# IO.net
KiCad netlist of a schematic drawn in Altium Designer
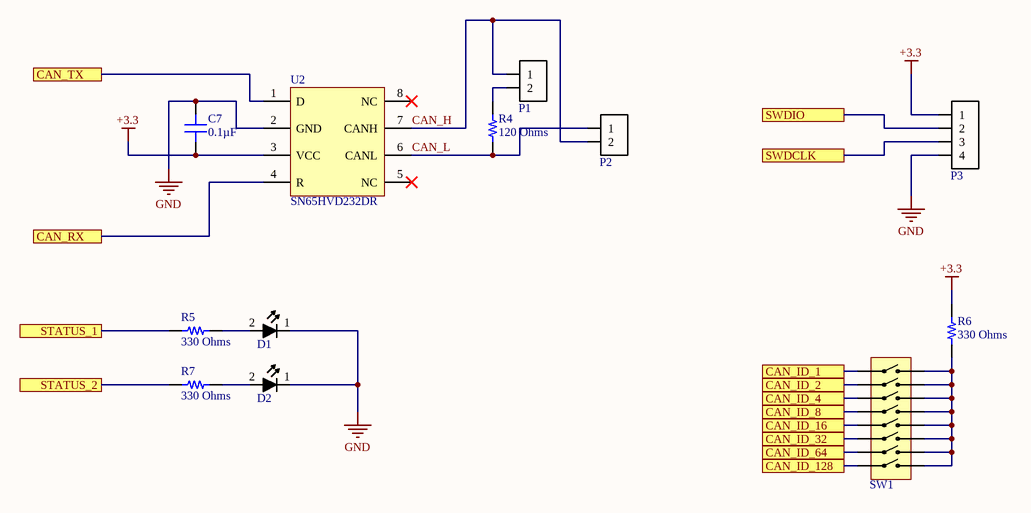
[diagram p0: IO.SchDoc]

(export (version "E")
  (design (tool "Eeschema 10.0.6"))
  (components
    (comp (ref "C7")
      (value "0.1µF")
      (footprint "CAP 0805_2012")
      (description "CAP CER 0805 0.1UF 50V X7R")
      (fields (field (name "PART NUMBER") "C0805X104K5RAC3316") (field (name "MANUFACTURER") "KEMET"))
      (libsource (lib "Celestial Altium Library - altium_library") (part "Capacitor"))
    )
    (comp (ref "D1")
      (value "diode_4")
      (footprint "chip_0603_LED")
      (description "LED, Blue, 0603, Low current, HELI2 Series")
      (fields (field (name "PART NUMBER") "DIO-00049") (field (name "MANUFACTURER") "Kingbright"))
      (libsource (lib "cwrubotix_library") (part "diode_4"))
    )
    (comp (ref "D2")
      (value "diode_4")
      (footprint "chip_0603_LED")
      (description "LED, Blue, 0603, Low current, HELI2 Series")
      (fields (field (name "PART NUMBER") "DIO-00049") (field (name "MANUFACTURER") "Kingbright"))
      (libsource (lib "cwrubotix_library") (part "diode_4"))
    )
    (comp (ref "P1")
      (value "conn-2x1_0")
      (footprint "hddr_2x1_0")
      (description "Header, 2x1, 0.1\"")
      (fields (field (name "PART NUMBER") "CONN-00055") (field (name "MANUFACTURER") "Samtec"))
      (libsource (lib "Connectors") (part "conn-2x1_0"))
    )
    (comp (ref "P2")
      (value "conn-2x1_0")
      (footprint "TERM_3.50MM_2x1_0")
      (description "Term Blk, 2 Pos, 8A, 3.5mm Pitch, Screwless")
      (fields (field (name "PART NUMBER") "CONN-00023") (field (name "MANUFACTURER") "Phoenix Contact"))
      (libsource (lib "Connectors") (part "conn-2x1_0"))
    )
    (comp (ref "P3")
      (value "conn-4x1_0")
      (footprint "HDDR_4x1_0")
      (description "Header 4x1, 0.1\"")
      (fields (field (name "PART NUMBER") "CONN-00029"))
      (libsource (lib "Connectors") (part "conn-4x1_0"))
    )
    (comp (ref "R4")
      (value "120 Ohms")
      (footprint "RES 0805_2012")
      (description "CRGCQ 0805 120R 1%")
      (fields
        (field (name "PART NUMBER") "CRGCQ0805F120R")
        (field (name "MANUFACTURER") "TE Connectivity Passive Product")
      )
      (libsource (lib "Celestial Altium Library - altium_library") (part "Resistor"))
    )
    (comp (ref "R5")
      (value "330 Ohms")
      (footprint "RES 0603_1608")
      (description "RES 330 OHM 5% 1/8W 0603")
      (fields
        (field (name "PART NUMBER") "RK73B1JTTD331J")
        (field (name "MANUFACTURER") "KOA Speer Electronics, Inc.")
      )
      (libsource (lib "Celestial Altium Library - altium_library") (part "Resistor"))
    )
    (comp (ref "R6")
      (value "330 Ohms")
      (footprint "RES 0603_1608")
      (description "RES 330 OHM 5% 1/8W 0603")
      (fields
        (field (name "PART NUMBER") "RK73B1JTTD331J")
        (field (name "MANUFACTURER") "KOA Speer Electronics, Inc.")
      )
      (libsource (lib "Celestial Altium Library - altium_library") (part "Resistor"))
    )
    (comp (ref "R7")
      (value "330 Ohms")
      (footprint "RES 0603_1608")
      (description "RES 330 OHM 5% 1/8W 0603")
      (fields
        (field (name "PART NUMBER") "RK73B1JTTD331J")
        (field (name "MANUFACTURER") "KOA Speer Electronics, Inc.")
      )
      (libsource (lib "Celestial Altium Library - altium_library") (part "Resistor"))
    )
    (comp (ref "SW1")
      (value "DIP_SW_8")
      (footprint "A6S-8104-H")
      (description "DIP Switch, 8 Switches, SMD, 25mA, 24V")
      (fields (field (name "PART NUMBER") "MISC-00045") (field (name "MANUFACTURER") "Omron"))
      (libsource (lib "Misc") (part "DIP_SW_8"))
    )
    (comp (ref "U2")
      (value "SN65HVD232")
      (footprint "SO-8")
      (description "CANbus Transceiver, Single channel, SN65HVD232")
      (fields
        (field (name "MANUFACTURER PN") "SN65HVD232DR")
        (field (name "PART NUMBER") "IFACE-00008")
        (field (name "MANUFACTURER") "TI")
      )
      (libsource (lib "Interfaces") (part "SN65HVD232"))
    )
  )
  (nets
    (net (code "1") (name "+3.3") (class "Default")
      (node (ref "C7") (pin "1") (pinfunction "1_1") (pintype "passive"))
      (node (ref "P3") (pin "1") (pinfunction "1_1") (pintype "passive"))
      (node (ref "R6") (pin "2") (pinfunction "2_2") (pintype "passive"))
      (node (ref "U2") (pin "3") (pinfunction "VCC_3") (pintype "passive"))
    )
    (net (code "2") (name "/CAN_H") (class "Default")
      (node (ref "P1") (pin "1") (pinfunction "1_1") (pintype "passive"))
      (node (ref "P2") (pin "2") (pinfunction "2_2") (pintype "passive"))
      (node (ref "U2") (pin "7") (pinfunction "CANH_7") (pintype "passive"))
    )
    (net (code "3") (name "/CAN_ID_1") (class "Default")
      (node (ref "SW1") (pin "1") (pinfunction "1_1") (pintype "passive"))
    )
    (net (code "4") (name "/CAN_ID_2") (class "Default")
      (node (ref "SW1") (pin "2") (pinfunction "2_2") (pintype "passive"))
    )
    (net (code "5") (name "/CAN_ID_4") (class "Default")
      (node (ref "SW1") (pin "3") (pinfunction "3_3") (pintype "passive"))
    )
    (net (code "6") (name "/CAN_ID_8") (class "Default")
      (node (ref "SW1") (pin "4") (pinfunction "4_4") (pintype "passive"))
    )
    (net (code "7") (name "/CAN_ID_16") (class "Default")
      (node (ref "SW1") (pin "5") (pinfunction "5_5") (pintype "passive"))
    )
    (net (code "8") (name "/CAN_ID_32") (class "Default")
      (node (ref "SW1") (pin "6") (pinfunction "6_6") (pintype "passive"))
    )
    (net (code "9") (name "/CAN_ID_64") (class "Default")
      (node (ref "SW1") (pin "7") (pinfunction "7_7") (pintype "passive"))
    )
    (net (code "10") (name "/CAN_ID_128") (class "Default")
      (node (ref "SW1") (pin "8") (pinfunction "8_8") (pintype "passive"))
    )
    (net (code "11") (name "/CAN_L") (class "Default")
      (node (ref "P2") (pin "1") (pinfunction "1_1") (pintype "passive"))
      (node (ref "R4") (pin "1") (pinfunction "1_1") (pintype "passive"))
      (node (ref "U2") (pin "6") (pinfunction "CANL_6") (pintype "passive"))
    )
    (net (code "12") (name "/CAN_RX") (class "Default")
      (node (ref "U2") (pin "4") (pinfunction "R_4") (pintype "passive"))
    )
    (net (code "13") (name "/CAN_TX") (class "Default")
      (node (ref "U2") (pin "1") (pinfunction "D_1") (pintype "passive"))
    )
    (net (code "14") (name "/STATUS_1") (class "Default")
      (node (ref "R5") (pin "1") (pinfunction "1_1") (pintype "passive"))
    )
    (net (code "15") (name "/STATUS_2") (class "Default")
      (node (ref "R7") (pin "1") (pinfunction "1_1") (pintype "passive"))
    )
    (net (code "16") (name "/SWDCLK") (class "Default")
      (node (ref "P3") (pin "3") (pinfunction "3_3") (pintype "passive"))
    )
    (net (code "17") (name "/SWDIO") (class "Default")
      (node (ref "P3") (pin "2") (pinfunction "2_2") (pintype "passive"))
    )
    (net (code "18") (name "GND") (class "Default")
      (node (ref "C7") (pin "2") (pinfunction "2_2") (pintype "passive"))
      (node (ref "D1") (pin "1") (pinfunction "1_1") (pintype "passive"))
      (node (ref "D2") (pin "1") (pinfunction "1_1") (pintype "passive"))
      (node (ref "P3") (pin "4") (pinfunction "4_4") (pintype "passive"))
      (node (ref "U2") (pin "2") (pinfunction "GND_2") (pintype "passive"))
    )
    (net (code "19") (name "Net-(D1-Pad2)") (class "Default")
      (node (ref "D1") (pin "2") (pinfunction "2_2") (pintype "passive"))
      (node (ref "R5") (pin "2") (pinfunction "2_2") (pintype "passive"))
    )
    (net (code "20") (name "Net-(D2-Pad2)") (class "Default")
      (node (ref "D2") (pin "2") (pinfunction "2_2") (pintype "passive"))
      (node (ref "R7") (pin "2") (pinfunction "2_2") (pintype "passive"))
    )
    (net (code "21") (name "Net-(P1-Pad2)") (class "Default")
      (node (ref "P1") (pin "2") (pinfunction "2_2") (pintype "passive"))
      (node (ref "R4") (pin "2") (pinfunction "2_2") (pintype "passive"))
    )
    (net (code "22") (name "Net-(R6-Pad1)") (class "Default")
      (node (ref "R6") (pin "1") (pinfunction "1_1") (pintype "passive"))
      (node (ref "SW1") (pin "10") (pinfunction "10_10") (pintype "passive"))
      (node (ref "SW1") (pin "11") (pinfunction "11_11") (pintype "passive"))
      (node (ref "SW1") (pin "12") (pinfunction "12_12") (pintype "passive"))
      (node (ref "SW1") (pin "13") (pinfunction "13_13") (pintype "passive"))
      (node (ref "SW1") (pin "14") (pinfunction "14_14") (pintype "passive"))
      (node (ref "SW1") (pin "15") (pinfunction "15_15") (pintype "passive"))
      (node (ref "SW1") (pin "16") (pinfunction "16_16") (pintype "passive"))
      (node (ref "SW1") (pin "9") (pinfunction "9_9") (pintype "passive"))
    )
    (net (code "23") (name "unconnected-(U2-NC-Pad5)") (class "Default")
      (node (ref "U2") (pin "5") (pinfunction "NC_5") (pintype "passive+no_connect"))
    )
    (net (code "24") (name "unconnected-(U2-NC-Pad8)") (class "Default")
      (node (ref "U2") (pin "8") (pinfunction "NC_8") (pintype "passive+no_connect"))
    )
  )
)
